# SnakeGame.net
KiCad netlist of a schematic drawn in EAGLE
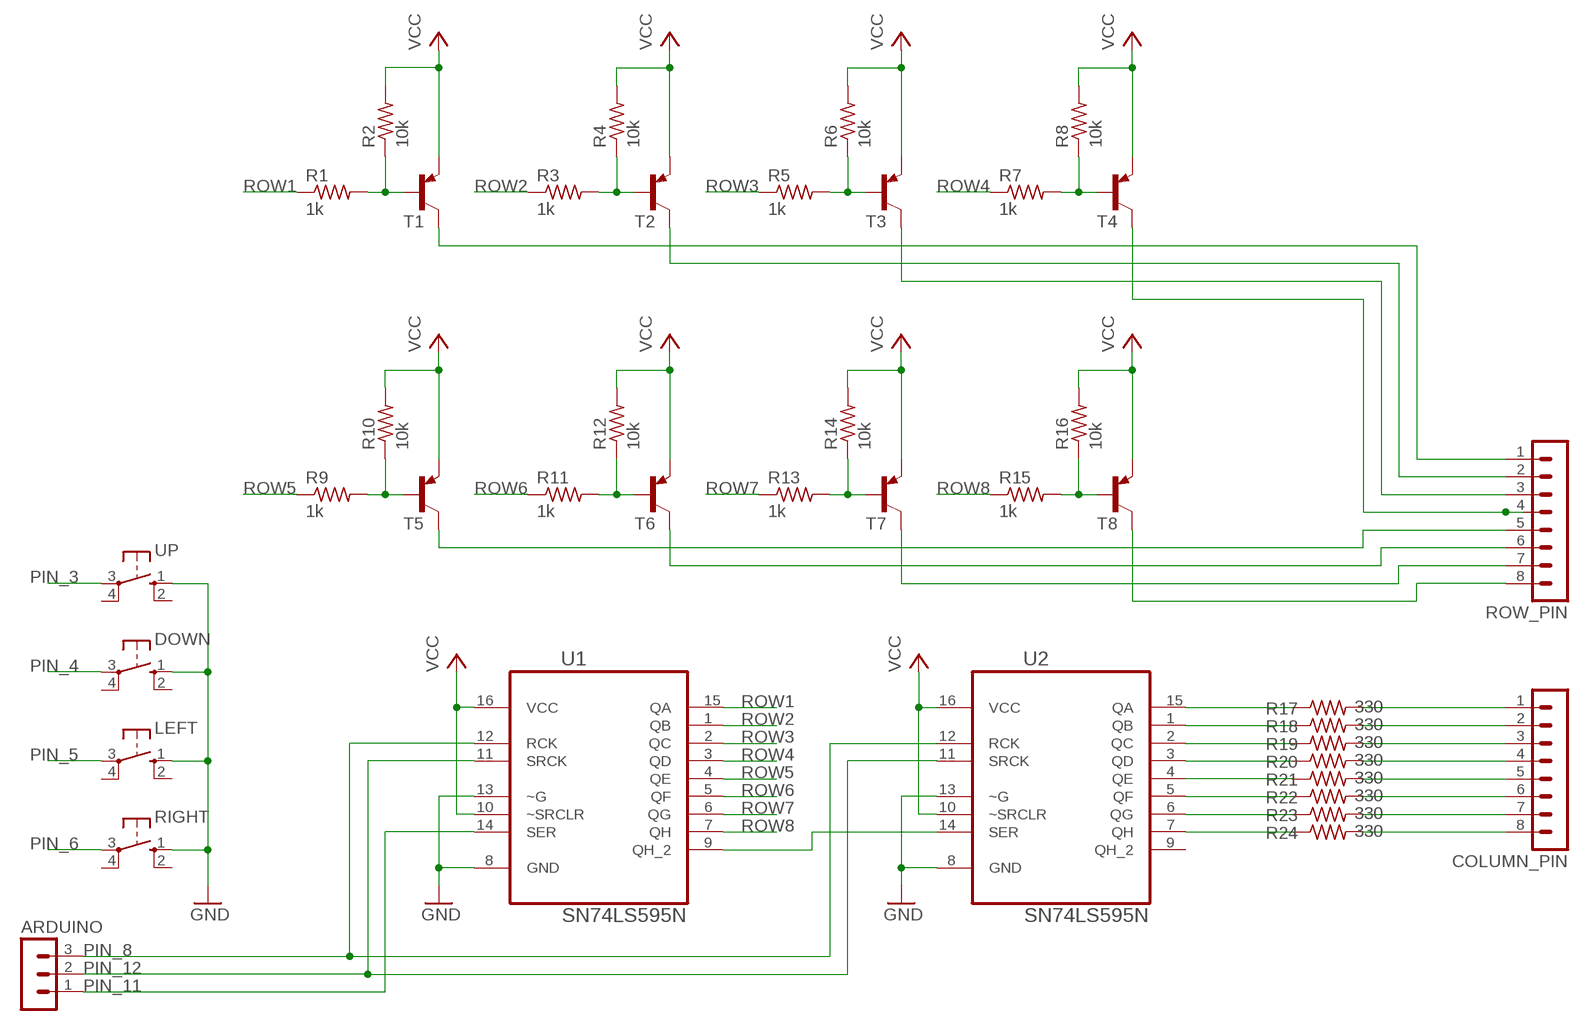
[diagram p0: schematic, sheet 1]

(export (version "E")
  (design (tool "Eeschema 10.0.6"))
  (components
    (comp (ref "ARDUINO")
      (value "MA03-1")
      (footprint "eagle-import:MA03-1")
      (libsource (lib "eagle-import") (part "MA03-1"))
    )
    (comp (ref "COLUMN_PIN")
      (value "MA08-1")
      (footprint "eagle-import:MA08-1")
      (libsource (lib "eagle-import") (part "MA08-1"))
    )
    (comp (ref "DOWN")
      (value "10-XX")
      (footprint "eagle-import:B3F-10XX")
      (fields (field (name "MPN") "B3F-1000"))
      (libsource (lib "eagle-import") (part "10-XX"))
    )
    (comp (ref "LEFT")
      (value "10-XX")
      (footprint "eagle-import:B3F-10XX")
      (fields (field (name "MPN") "B3F-1000"))
      (libsource (lib "eagle-import") (part "10-XX"))
    )
    (comp (ref "R1")
      (value "1k")
      (footprint "eagle-import:0204_7")
      (libsource (lib "eagle-import") (part "resistor_R-US_0204/7"))
    )
    (comp (ref "R2")
      (value "10k")
      (footprint "eagle-import:0204_7")
      (libsource (lib "eagle-import") (part "resistor_R-US_0204/7"))
    )
    (comp (ref "R3")
      (value "1k")
      (footprint "eagle-import:0204_7")
      (libsource (lib "eagle-import") (part "resistor_R-US_0204/7"))
    )
    (comp (ref "R4")
      (value "10k")
      (footprint "eagle-import:0204_7")
      (libsource (lib "eagle-import") (part "resistor_R-US_0204/7"))
    )
    (comp (ref "R5")
      (value "1k")
      (footprint "eagle-import:0204_7")
      (libsource (lib "eagle-import") (part "resistor_R-US_0204/7"))
    )
    (comp (ref "R6")
      (value "10k")
      (footprint "eagle-import:0204_7")
      (libsource (lib "eagle-import") (part "resistor_R-US_0204/7"))
    )
    (comp (ref "R7")
      (value "1k")
      (footprint "eagle-import:0204_7")
      (libsource (lib "eagle-import") (part "resistor_R-US_0204/7"))
    )
    (comp (ref "R8")
      (value "10k")
      (footprint "eagle-import:0204_7")
      (libsource (lib "eagle-import") (part "resistor_R-US_0204/7"))
    )
    (comp (ref "R9")
      (value "1k")
      (footprint "eagle-import:0204_7")
      (libsource (lib "eagle-import") (part "resistor_R-US_0204/7"))
    )
    (comp (ref "R10")
      (value "10k")
      (footprint "eagle-import:0204_7")
      (libsource (lib "eagle-import") (part "resistor_R-US_0204/7"))
    )
    (comp (ref "R11")
      (value "1k")
      (footprint "eagle-import:0204_7")
      (libsource (lib "eagle-import") (part "resistor_R-US_0204/7"))
    )
    (comp (ref "R12")
      (value "10k")
      (footprint "eagle-import:0204_7")
      (libsource (lib "eagle-import") (part "resistor_R-US_0204/7"))
    )
    (comp (ref "R13")
      (value "1k")
      (footprint "eagle-import:0204_7")
      (libsource (lib "eagle-import") (part "resistor_R-US_0204/7"))
    )
    (comp (ref "R14")
      (value "10k")
      (footprint "eagle-import:0204_7")
      (libsource (lib "eagle-import") (part "resistor_R-US_0204/7"))
    )
    (comp (ref "R15")
      (value "1k")
      (footprint "eagle-import:0204_7")
      (libsource (lib "eagle-import") (part "resistor_R-US_0204/7"))
    )
    (comp (ref "R16")
      (value "10k")
      (footprint "eagle-import:0204_7")
      (libsource (lib "eagle-import") (part "resistor_R-US_0204/7"))
    )
    (comp (ref "R17")
      (value "330")
      (footprint "eagle-import:0204_7")
      (libsource (lib "eagle-import") (part "R-US_0204/7"))
    )
    (comp (ref "R18")
      (value "330")
      (footprint "eagle-import:0204_7")
      (libsource (lib "eagle-import") (part "R-US_0204/7"))
    )
    (comp (ref "R19")
      (value "330")
      (footprint "eagle-import:0204_7")
      (libsource (lib "eagle-import") (part "R-US_0204/7"))
    )
    (comp (ref "R20")
      (value "330")
      (footprint "eagle-import:0204_7")
      (libsource (lib "eagle-import") (part "R-US_0204/7"))
    )
    (comp (ref "R21")
      (value "330")
      (footprint "eagle-import:0204_7")
      (libsource (lib "eagle-import") (part "R-US_0204/7"))
    )
    (comp (ref "R22")
      (value "330")
      (footprint "eagle-import:0204_7")
      (libsource (lib "eagle-import") (part "R-US_0204/7"))
    )
    (comp (ref "R23")
      (value "330")
      (footprint "eagle-import:0204_7")
      (libsource (lib "eagle-import") (part "R-US_0204/7"))
    )
    (comp (ref "R24")
      (value "330")
      (footprint "eagle-import:0204_7")
      (libsource (lib "eagle-import") (part "R-US_0204/7"))
    )
    (comp (ref "RIGHT")
      (value "10-XX")
      (footprint "eagle-import:B3F-10XX")
      (fields (field (name "MPN") "B3F-1000"))
      (libsource (lib "eagle-import") (part "10-XX"))
    )
    (comp (ref "ROW_PIN")
      (value "MA08-1")
      (footprint "eagle-import:MA08-1")
      (libsource (lib "eagle-import") (part "MA08-1"))
    )
    (comp (ref "T1")
      (value "-PNP-TO92")
      (footprint "eagle-import:TO92")
      (libsource (lib "eagle-import") (part "-PNP-TO92"))
    )
    (comp (ref "T2")
      (value "-PNP-TO92")
      (footprint "eagle-import:TO92")
      (libsource (lib "eagle-import") (part "-PNP-TO92"))
    )
    (comp (ref "T3")
      (value "-PNP-TO92")
      (footprint "eagle-import:TO92")
      (libsource (lib "eagle-import") (part "-PNP-TO92"))
    )
    (comp (ref "T4")
      (value "-PNP-TO92")
      (footprint "eagle-import:TO92")
      (libsource (lib "eagle-import") (part "-PNP-TO92"))
    )
    (comp (ref "T5")
      (value "-PNP-TO92")
      (footprint "eagle-import:TO92")
      (libsource (lib "eagle-import") (part "-PNP-TO92"))
    )
    (comp (ref "T6")
      (value "-PNP-TO92")
      (footprint "eagle-import:TO92")
      (libsource (lib "eagle-import") (part "-PNP-TO92"))
    )
    (comp (ref "T7")
      (value "-PNP-TO92")
      (footprint "eagle-import:TO92")
      (libsource (lib "eagle-import") (part "-PNP-TO92"))
    )
    (comp (ref "T8")
      (value "-PNP-TO92")
      (footprint "eagle-import:TO92")
      (libsource (lib "eagle-import") (part "-PNP-TO92"))
    )
    (comp (ref "U1")
      (value "SN74LS595N")
      (footprint "eagle-import:DIP254P762X508-16")
      (libsource (lib "eagle-import") (part "SN74LS595N"))
    )
    (comp (ref "U2")
      (value "SN74LS595N")
      (footprint "eagle-import:DIP254P762X508-16")
      (libsource (lib "eagle-import") (part "SN74LS595N"))
    )
    (comp (ref "UP")
      (value "10-XX")
      (footprint "eagle-import:B3F-10XX")
      (fields (field (name "MPN") "B3F-1000"))
      (libsource (lib "eagle-import") (part "10-XX"))
    )
  )
  (nets
    (net (code "1") (name "/PIN_3") (class "Default")
      (node (ref "UP") (pin "3") (pinfunction "P_3") (pintype "passive"))
    )
    (net (code "2") (name "/PIN_4") (class "Default")
      (node (ref "DOWN") (pin "3") (pinfunction "P_3") (pintype "passive"))
    )
    (net (code "3") (name "/PIN_5") (class "Default")
      (node (ref "LEFT") (pin "3") (pinfunction "P_3") (pintype "passive"))
    )
    (net (code "4") (name "/PIN_6") (class "Default")
      (node (ref "RIGHT") (pin "3") (pinfunction "P_3") (pintype "passive"))
    )
    (net (code "5") (name "/PIN_8") (class "Default")
      (node (ref "ARDUINO") (pin "3") (pinfunction "3_3") (pintype "passive"))
      (node (ref "U1") (pin "12") (pinfunction "RCK_12") (pintype "input"))
      (node (ref "U2") (pin "12") (pinfunction "RCK_12") (pintype "input"))
    )
    (net (code "6") (name "/PIN_11") (class "Default")
      (node (ref "ARDUINO") (pin "1") (pinfunction "1_1") (pintype "passive"))
      (node (ref "U1") (pin "14") (pinfunction "SER_14") (pintype "input"))
    )
    (net (code "7") (name "/PIN_12") (class "Default")
      (node (ref "ARDUINO") (pin "2") (pinfunction "2_2") (pintype "passive"))
      (node (ref "U1") (pin "11") (pinfunction "SRCK_11") (pintype "input"))
      (node (ref "U2") (pin "11") (pinfunction "SRCK_11") (pintype "input"))
    )
    (net (code "8") (name "/ROW1") (class "Default")
      (node (ref "R1") (pin "1") (pinfunction "1_1") (pintype "passive"))
      (node (ref "U1") (pin "15") (pinfunction "QA_15") (pintype "output"))
    )
    (net (code "9") (name "/ROW2") (class "Default")
      (node (ref "R3") (pin "1") (pinfunction "1_1") (pintype "passive"))
      (node (ref "U1") (pin "1") (pinfunction "QB_1") (pintype "output"))
    )
    (net (code "10") (name "/ROW3") (class "Default")
      (node (ref "R5") (pin "1") (pinfunction "1_1") (pintype "passive"))
      (node (ref "U1") (pin "2") (pinfunction "QC_2") (pintype "output"))
    )
    (net (code "11") (name "/ROW4") (class "Default")
      (node (ref "R7") (pin "1") (pinfunction "1_1") (pintype "passive"))
      (node (ref "U1") (pin "3") (pinfunction "QD_3") (pintype "output"))
    )
    (net (code "12") (name "/ROW5") (class "Default")
      (node (ref "R9") (pin "1") (pinfunction "1_1") (pintype "passive"))
      (node (ref "U1") (pin "4") (pinfunction "QE_4") (pintype "output"))
    )
    (net (code "13") (name "/ROW6") (class "Default")
      (node (ref "R11") (pin "1") (pinfunction "1_1") (pintype "passive"))
      (node (ref "U1") (pin "5") (pinfunction "QF_5") (pintype "output"))
    )
    (net (code "14") (name "/ROW7") (class "Default")
      (node (ref "R13") (pin "1") (pinfunction "1_1") (pintype "passive"))
      (node (ref "U1") (pin "6") (pinfunction "QG_6") (pintype "output"))
    )
    (net (code "15") (name "/ROW8") (class "Default")
      (node (ref "R15") (pin "1") (pinfunction "1_1") (pintype "passive"))
      (node (ref "U1") (pin "7") (pinfunction "QH_7") (pintype "output"))
    )
    (net (code "16") (name "GND") (class "Default")
      (node (ref "DOWN") (pin "1") (pinfunction "S_1") (pintype "passive"))
      (node (ref "LEFT") (pin "1") (pinfunction "S_1") (pintype "passive"))
      (node (ref "RIGHT") (pin "1") (pinfunction "S_1") (pintype "passive"))
      (node (ref "U1") (pin "13") (pinfunction "~{G}_13") (pintype "input"))
      (node (ref "U1") (pin "8") (pinfunction "GND_8") (pintype "passive"))
      (node (ref "U2") (pin "13") (pinfunction "~{G}_13") (pintype "input"))
      (node (ref "U2") (pin "8") (pinfunction "GND_8") (pintype "passive"))
      (node (ref "UP") (pin "1") (pinfunction "S_1") (pintype "passive"))
    )
    (net (code "17") (name "Net-(COLUMN_PIN-Pad1)") (class "Default")
      (node (ref "COLUMN_PIN") (pin "1") (pinfunction "1_1") (pintype "passive"))
      (node (ref "R17") (pin "2") (pinfunction "2_2") (pintype "passive"))
    )
    (net (code "18") (name "Net-(COLUMN_PIN-Pad2)") (class "Default")
      (node (ref "COLUMN_PIN") (pin "2") (pinfunction "2_2") (pintype "passive"))
      (node (ref "R18") (pin "2") (pinfunction "2_2") (pintype "passive"))
    )
    (net (code "19") (name "Net-(COLUMN_PIN-Pad3)") (class "Default")
      (node (ref "COLUMN_PIN") (pin "3") (pinfunction "3_3") (pintype "passive"))
      (node (ref "R19") (pin "2") (pinfunction "2_2") (pintype "passive"))
    )
    (net (code "20") (name "Net-(COLUMN_PIN-Pad4)") (class "Default")
      (node (ref "COLUMN_PIN") (pin "4") (pinfunction "4_4") (pintype "passive"))
      (node (ref "R20") (pin "2") (pinfunction "2_2") (pintype "passive"))
    )
    (net (code "21") (name "Net-(COLUMN_PIN-Pad5)") (class "Default")
      (node (ref "COLUMN_PIN") (pin "5") (pinfunction "5_5") (pintype "passive"))
      (node (ref "R21") (pin "2") (pinfunction "2_2") (pintype "passive"))
    )
    (net (code "22") (name "Net-(COLUMN_PIN-Pad6)") (class "Default")
      (node (ref "COLUMN_PIN") (pin "6") (pinfunction "6_6") (pintype "passive"))
      (node (ref "R22") (pin "2") (pinfunction "2_2") (pintype "passive"))
    )
    (net (code "23") (name "Net-(COLUMN_PIN-Pad7)") (class "Default")
      (node (ref "COLUMN_PIN") (pin "7") (pinfunction "7_7") (pintype "passive"))
      (node (ref "R23") (pin "2") (pinfunction "2_2") (pintype "passive"))
    )
    (net (code "24") (name "Net-(COLUMN_PIN-Pad8)") (class "Default")
      (node (ref "COLUMN_PIN") (pin "8") (pinfunction "8_8") (pintype "passive"))
      (node (ref "R24") (pin "2") (pinfunction "2_2") (pintype "passive"))
    )
    (net (code "25") (name "Net-(T1-B)") (class "Default")
      (node (ref "R1") (pin "2") (pinfunction "2_2") (pintype "passive"))
      (node (ref "R2") (pin "1") (pinfunction "1_1") (pintype "passive"))
      (node (ref "T1") (pin "2") (pinfunction "B_2") (pintype "passive"))
    )
    (net (code "26") (name "Net-(T1-C)") (class "Default")
      (node (ref "ROW_PIN") (pin "1") (pinfunction "1_1") (pintype "passive"))
      (node (ref "T1") (pin "3") (pinfunction "C_3") (pintype "passive"))
    )
    (net (code "27") (name "Net-(T2-B)") (class "Default")
      (node (ref "R3") (pin "2") (pinfunction "2_2") (pintype "passive"))
      (node (ref "R4") (pin "1") (pinfunction "1_1") (pintype "passive"))
      (node (ref "T2") (pin "2") (pinfunction "B_2") (pintype "passive"))
    )
    (net (code "28") (name "Net-(T2-C)") (class "Default")
      (node (ref "ROW_PIN") (pin "2") (pinfunction "2_2") (pintype "passive"))
      (node (ref "T2") (pin "3") (pinfunction "C_3") (pintype "passive"))
    )
    (net (code "29") (name "Net-(T3-B)") (class "Default")
      (node (ref "R5") (pin "2") (pinfunction "2_2") (pintype "passive"))
      (node (ref "R6") (pin "1") (pinfunction "1_1") (pintype "passive"))
      (node (ref "T3") (pin "2") (pinfunction "B_2") (pintype "passive"))
    )
    (net (code "30") (name "Net-(T3-C)") (class "Default")
      (node (ref "ROW_PIN") (pin "3") (pinfunction "3_3") (pintype "passive"))
      (node (ref "T3") (pin "3") (pinfunction "C_3") (pintype "passive"))
    )
    (net (code "31") (name "Net-(T4-B)") (class "Default")
      (node (ref "R7") (pin "2") (pinfunction "2_2") (pintype "passive"))
      (node (ref "R8") (pin "1") (pinfunction "1_1") (pintype "passive"))
      (node (ref "T4") (pin "2") (pinfunction "B_2") (pintype "passive"))
    )
    (net (code "32") (name "Net-(T4-C)") (class "Default")
      (node (ref "ROW_PIN") (pin "4") (pinfunction "4_4") (pintype "passive"))
      (node (ref "T4") (pin "3") (pinfunction "C_3") (pintype "passive"))
    )
    (net (code "33") (name "Net-(T5-B)") (class "Default")
      (node (ref "R10") (pin "1") (pinfunction "1_1") (pintype "passive"))
      (node (ref "R9") (pin "2") (pinfunction "2_2") (pintype "passive"))
      (node (ref "T5") (pin "2") (pinfunction "B_2") (pintype "passive"))
    )
    (net (code "34") (name "Net-(T5-C)") (class "Default")
      (node (ref "ROW_PIN") (pin "5") (pinfunction "5_5") (pintype "passive"))
      (node (ref "T5") (pin "3") (pinfunction "C_3") (pintype "passive"))
    )
    (net (code "35") (name "Net-(T6-B)") (class "Default")
      (node (ref "R11") (pin "2") (pinfunction "2_2") (pintype "passive"))
      (node (ref "R12") (pin "1") (pinfunction "1_1") (pintype "passive"))
      (node (ref "T6") (pin "2") (pinfunction "B_2") (pintype "passive"))
    )
    (net (code "36") (name "Net-(T6-C)") (class "Default")
      (node (ref "ROW_PIN") (pin "6") (pinfunction "6_6") (pintype "passive"))
      (node (ref "T6") (pin "3") (pinfunction "C_3") (pintype "passive"))
    )
    (net (code "37") (name "Net-(T7-B)") (class "Default")
      (node (ref "R13") (pin "2") (pinfunction "2_2") (pintype "passive"))
      (node (ref "R14") (pin "1") (pinfunction "1_1") (pintype "passive"))
      (node (ref "T7") (pin "2") (pinfunction "B_2") (pintype "passive"))
    )
    (net (code "38") (name "Net-(T7-C)") (class "Default")
      (node (ref "ROW_PIN") (pin "7") (pinfunction "7_7") (pintype "passive"))
      (node (ref "T7") (pin "3") (pinfunction "C_3") (pintype "passive"))
    )
    (net (code "39") (name "Net-(T8-B)") (class "Default")
      (node (ref "R15") (pin "2") (pinfunction "2_2") (pintype "passive"))
      (node (ref "R16") (pin "1") (pinfunction "1_1") (pintype "passive"))
      (node (ref "T8") (pin "2") (pinfunction "B_2") (pintype "passive"))
    )
    (net (code "40") (name "Net-(T8-C)") (class "Default")
      (node (ref "ROW_PIN") (pin "8") (pinfunction "8_8") (pintype "passive"))
      (node (ref "T8") (pin "3") (pinfunction "C_3") (pintype "passive"))
    )
    (net (code "41") (name "Net-(U1-QH_2)") (class "Default")
      (node (ref "U1") (pin "9") (pinfunction "QH_2_9") (pintype "output"))
      (node (ref "U2") (pin "14") (pinfunction "SER_14") (pintype "input"))
    )
    (net (code "42") (name "Net-(U2-QA)") (class "Default")
      (node (ref "R17") (pin "1") (pinfunction "1_1") (pintype "passive"))
      (node (ref "U2") (pin "15") (pinfunction "QA_15") (pintype "output"))
    )
    (net (code "43") (name "Net-(U2-QB)") (class "Default")
      (node (ref "R18") (pin "1") (pinfunction "1_1") (pintype "passive"))
      (node (ref "U2") (pin "1") (pinfunction "QB_1") (pintype "output"))
    )
    (net (code "44") (name "Net-(U2-QC)") (class "Default")
      (node (ref "R19") (pin "1") (pinfunction "1_1") (pintype "passive"))
      (node (ref "U2") (pin "2") (pinfunction "QC_2") (pintype "output"))
    )
    (net (code "45") (name "Net-(U2-QD)") (class "Default")
      (node (ref "R20") (pin "1") (pinfunction "1_1") (pintype "passive"))
      (node (ref "U2") (pin "3") (pinfunction "QD_3") (pintype "output"))
    )
    (net (code "46") (name "Net-(U2-QE)") (class "Default")
      (node (ref "R21") (pin "1") (pinfunction "1_1") (pintype "passive"))
      (node (ref "U2") (pin "4") (pinfunction "QE_4") (pintype "output"))
    )
    (net (code "47") (name "Net-(U2-QF)") (class "Default")
      (node (ref "R22") (pin "1") (pinfunction "1_1") (pintype "passive"))
      (node (ref "U2") (pin "5") (pinfunction "QF_5") (pintype "output"))
    )
    (net (code "48") (name "Net-(U2-QG)") (class "Default")
      (node (ref "R23") (pin "1") (pinfunction "1_1") (pintype "passive"))
      (node (ref "U2") (pin "6") (pinfunction "QG_6") (pintype "output"))
    )
    (net (code "49") (name "Net-(U2-QH)") (class "Default")
      (node (ref "R24") (pin "1") (pinfunction "1_1") (pintype "passive"))
      (node (ref "U2") (pin "7") (pinfunction "QH_7") (pintype "output"))
    )
    (net (code "50") (name "VCC") (class "Default")
      (node (ref "R10") (pin "2") (pinfunction "2_2") (pintype "passive"))
      (node (ref "R12") (pin "2") (pinfunction "2_2") (pintype "passive"))
      (node (ref "R14") (pin "2") (pinfunction "2_2") (pintype "passive"))
      (node (ref "R16") (pin "2") (pinfunction "2_2") (pintype "passive"))
      (node (ref "R2") (pin "2") (pinfunction "2_2") (pintype "passive"))
      (node (ref "R4") (pin "2") (pinfunction "2_2") (pintype "passive"))
      (node (ref "R6") (pin "2") (pinfunction "2_2") (pintype "passive"))
      (node (ref "R8") (pin "2") (pinfunction "2_2") (pintype "passive"))
      (node (ref "T1") (pin "1") (pinfunction "E_1") (pintype "passive"))
      (node (ref "T2") (pin "1") (pinfunction "E_1") (pintype "passive"))
      (node (ref "T3") (pin "1") (pinfunction "E_1") (pintype "passive"))
      (node (ref "T4") (pin "1") (pinfunction "E_1") (pintype "passive"))
      (node (ref "T5") (pin "1") (pinfunction "E_1") (pintype "passive"))
      (node (ref "T6") (pin "1") (pinfunction "E_1") (pintype "passive"))
      (node (ref "T7") (pin "1") (pinfunction "E_1") (pintype "passive"))
      (node (ref "T8") (pin "1") (pinfunction "E_1") (pintype "passive"))
      (node (ref "U1") (pin "10") (pinfunction "~{SRCLR}_10") (pintype "input"))
      (node (ref "U1") (pin "16") (pinfunction "VCC_16") (pintype "power_in"))
      (node (ref "U2") (pin "10") (pinfunction "~{SRCLR}_10") (pintype "input"))
      (node (ref "U2") (pin "16") (pinfunction "VCC_16") (pintype "power_in"))
    )
    (net (code "51") (name "unconnected-(DOWN-P1-Pad4)") (class "Default")
      (node (ref "DOWN") (pin "4") (pinfunction "P1_4") (pintype "passive"))
    )
    (net (code "52") (name "unconnected-(DOWN-S1-Pad2)") (class "Default")
      (node (ref "DOWN") (pin "2") (pinfunction "S1_2") (pintype "passive"))
    )
    (net (code "53") (name "unconnected-(LEFT-P1-Pad4)") (class "Default")
      (node (ref "LEFT") (pin "4") (pinfunction "P1_4") (pintype "passive"))
    )
    (net (code "54") (name "unconnected-(LEFT-S1-Pad2)") (class "Default")
      (node (ref "LEFT") (pin "2") (pinfunction "S1_2") (pintype "passive"))
    )
    (net (code "55") (name "unconnected-(RIGHT-P1-Pad4)") (class "Default")
      (node (ref "RIGHT") (pin "4") (pinfunction "P1_4") (pintype "passive"))
    )
    (net (code "56") (name "unconnected-(RIGHT-S1-Pad2)") (class "Default")
      (node (ref "RIGHT") (pin "2") (pinfunction "S1_2") (pintype "passive"))
    )
    (net (code "57") (name "unconnected-(U2-QH_2-Pad9)") (class "Default")
      (node (ref "U2") (pin "9") (pinfunction "QH_2_9") (pintype "output"))
    )
    (net (code "58") (name "unconnected-(UP-P1-Pad4)") (class "Default")
      (node (ref "UP") (pin "4") (pinfunction "P1_4") (pintype "passive"))
    )
    (net (code "59") (name "unconnected-(UP-S1-Pad2)") (class "Default")
      (node (ref "UP") (pin "2") (pinfunction "S1_2") (pintype "passive"))
    )
  )
)
